# AT42QT2120-breakout-v0.net
KiCad netlist of a schematic drawn in EAGLE
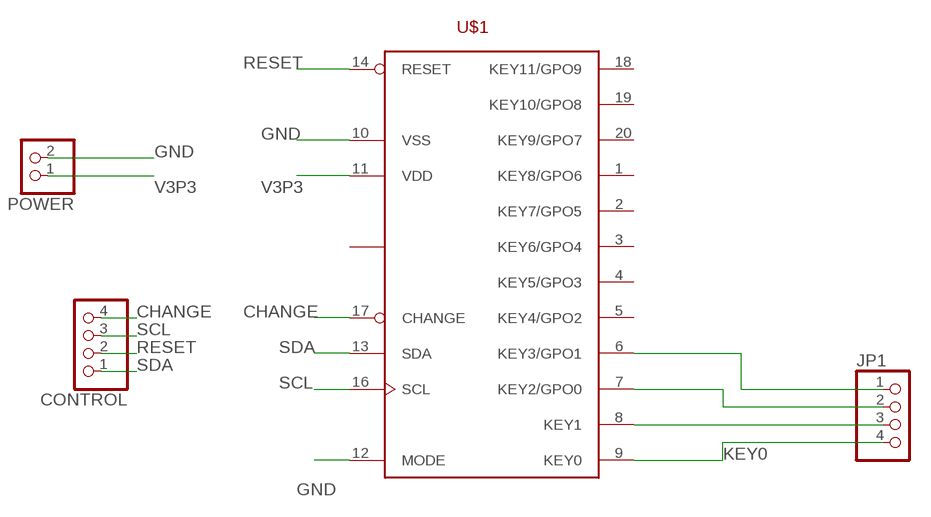
[diagram p0: schematic, sheet 1]

(export (version "E")
  (design (tool "Eeschema 10.0.6"))
  (components
    (comp (ref "CONTROL")
      (value "PINHD-1X4/90")
      (footprint "eagle-import:1X04_90")
      (libsource (lib "eagle-import") (part "PINHD-1X4/90"))
    )
    (comp (ref "JP1")
      (value "PINHD-1X4/90")
      (footprint "eagle-import:1X04_90")
      (libsource (lib "eagle-import") (part "PINHD-1X4/90"))
    )
    (comp (ref "POWER")
      (value "PINHD-1X2/90")
      (footprint "eagle-import:1X02_90")
      (libsource (lib "eagle-import") (part "PINHD-1X2/90"))
    )
    (comp (ref "U$1")
      (value "COMMS-AT42QT2120SU")
      (footprint "eagle-import:SO20W")
      (libsource (lib "eagle-import") (part "COMMS-AT42QT2120SU"))
    )
  )
  (nets
    (net (code "1") (name "/CHANGE") (class "Default")
      (node (ref "CONTROL") (pin "4") (pinfunction "4_4") (pintype "passive"))
      (node (ref "U$1") (pin "17") (pinfunction "CHANGE_17") (pintype "open_collector"))
    )
    (net (code "2") (name "/GND") (class "Default")
      (node (ref "POWER") (pin "2") (pinfunction "2_2") (pintype "passive"))
      (node (ref "U$1") (pin "10") (pinfunction "VSS_10") (pintype "power_in"))
      (node (ref "U$1") (pin "12") (pinfunction "MODE_12") (pintype "input"))
    )
    (net (code "3") (name "/KEY0") (class "Default")
      (node (ref "JP1") (pin "4") (pinfunction "4_4") (pintype "passive"))
      (node (ref "U$1") (pin "9") (pinfunction "KEY0_9") (pintype "bidirectional"))
    )
    (net (code "4") (name "/RESET") (class "Default")
      (node (ref "CONTROL") (pin "2") (pinfunction "2_2") (pintype "passive"))
      (node (ref "U$1") (pin "14") (pinfunction "RESET_14") (pintype "input"))
    )
    (net (code "5") (name "/SCL") (class "Default")
      (node (ref "CONTROL") (pin "3") (pinfunction "3_3") (pintype "passive"))
      (node (ref "U$1") (pin "16") (pinfunction "SCL_16") (pintype "open_collector"))
    )
    (net (code "6") (name "/SDA") (class "Default")
      (node (ref "CONTROL") (pin "1") (pinfunction "1_1") (pintype "passive"))
      (node (ref "U$1") (pin "13") (pinfunction "SDA_13") (pintype "open_collector"))
    )
    (net (code "7") (name "/V3P3") (class "Default")
      (node (ref "POWER") (pin "1") (pinfunction "1_1") (pintype "passive"))
      (node (ref "U$1") (pin "11") (pinfunction "VDD_11") (pintype "power_in"))
    )
    (net (code "8") (name "Net-(U$1-KEY1)") (class "Default")
      (node (ref "JP1") (pin "3") (pinfunction "3_3") (pintype "passive"))
      (node (ref "U$1") (pin "8") (pinfunction "KEY1_8") (pintype "bidirectional"))
    )
    (net (code "9") (name "Net-(U$1-KEY2{slash}GPO0)") (class "Default")
      (node (ref "JP1") (pin "2") (pinfunction "2_2") (pintype "passive"))
      (node (ref "U$1") (pin "7") (pinfunction "KEY2/GPO0_7") (pintype "bidirectional"))
    )
    (net (code "10") (name "Net-(U$1-KEY3{slash}GPO1)") (class "Default")
      (node (ref "JP1") (pin "1") (pinfunction "1_1") (pintype "passive"))
      (node (ref "U$1") (pin "6") (pinfunction "KEY3/GPO1_6") (pintype "bidirectional"))
    )
    (net (code "11") (name "unconnected-(U$1-KEY4{slash}GPO2-Pad5)") (class "Default")
      (node (ref "U$1") (pin "5") (pinfunction "KEY4/GPO2_5") (pintype "bidirectional"))
    )
    (net (code "12") (name "unconnected-(U$1-KEY5{slash}GPO3-Pad4)") (class "Default")
      (node (ref "U$1") (pin "4") (pinfunction "KEY5/GPO3_4") (pintype "bidirectional"))
    )
    (net (code "13") (name "unconnected-(U$1-KEY6{slash}GPO4-Pad3)") (class "Default")
      (node (ref "U$1") (pin "3") (pinfunction "KEY6/GPO4_3") (pintype "bidirectional"))
    )
    (net (code "14") (name "unconnected-(U$1-KEY7{slash}GPO5-Pad2)") (class "Default")
      (node (ref "U$1") (pin "2") (pinfunction "KEY7/GPO5_2") (pintype "bidirectional"))
    )
    (net (code "15") (name "unconnected-(U$1-KEY8{slash}GPO6-Pad1)") (class "Default")
      (node (ref "U$1") (pin "1") (pinfunction "KEY8/GPO6_1") (pintype "bidirectional"))
    )
    (net (code "16") (name "unconnected-(U$1-KEY9{slash}GPO7-Pad20)") (class "Default")
      (node (ref "U$1") (pin "20") (pinfunction "KEY9/GPO7_20") (pintype "bidirectional"))
    )
    (net (code "17") (name "unconnected-(U$1-KEY10{slash}GPO8-Pad19)") (class "Default")
      (node (ref "U$1") (pin "19") (pinfunction "KEY10/GPO8_19") (pintype "bidirectional"))
    )
    (net (code "18") (name "unconnected-(U$1-KEY11{slash}GPO9-Pad18)") (class "Default")
      (node (ref "U$1") (pin "18") (pinfunction "KEY11/GPO9_18") (pintype "bidirectional"))
    )
    (net (code "19") (name "unconnected-(U$1-NC-Pad15)") (class "Default")
      (node (ref "U$1") (pin "15") (pinfunction "NC_15") (pintype "no_connect"))
    )
  )
)
